# UBC-Thunderbots_PCB_Power__power-v3_1_pc.net
KiCad netlist of a schematic drawn in Altium Designer
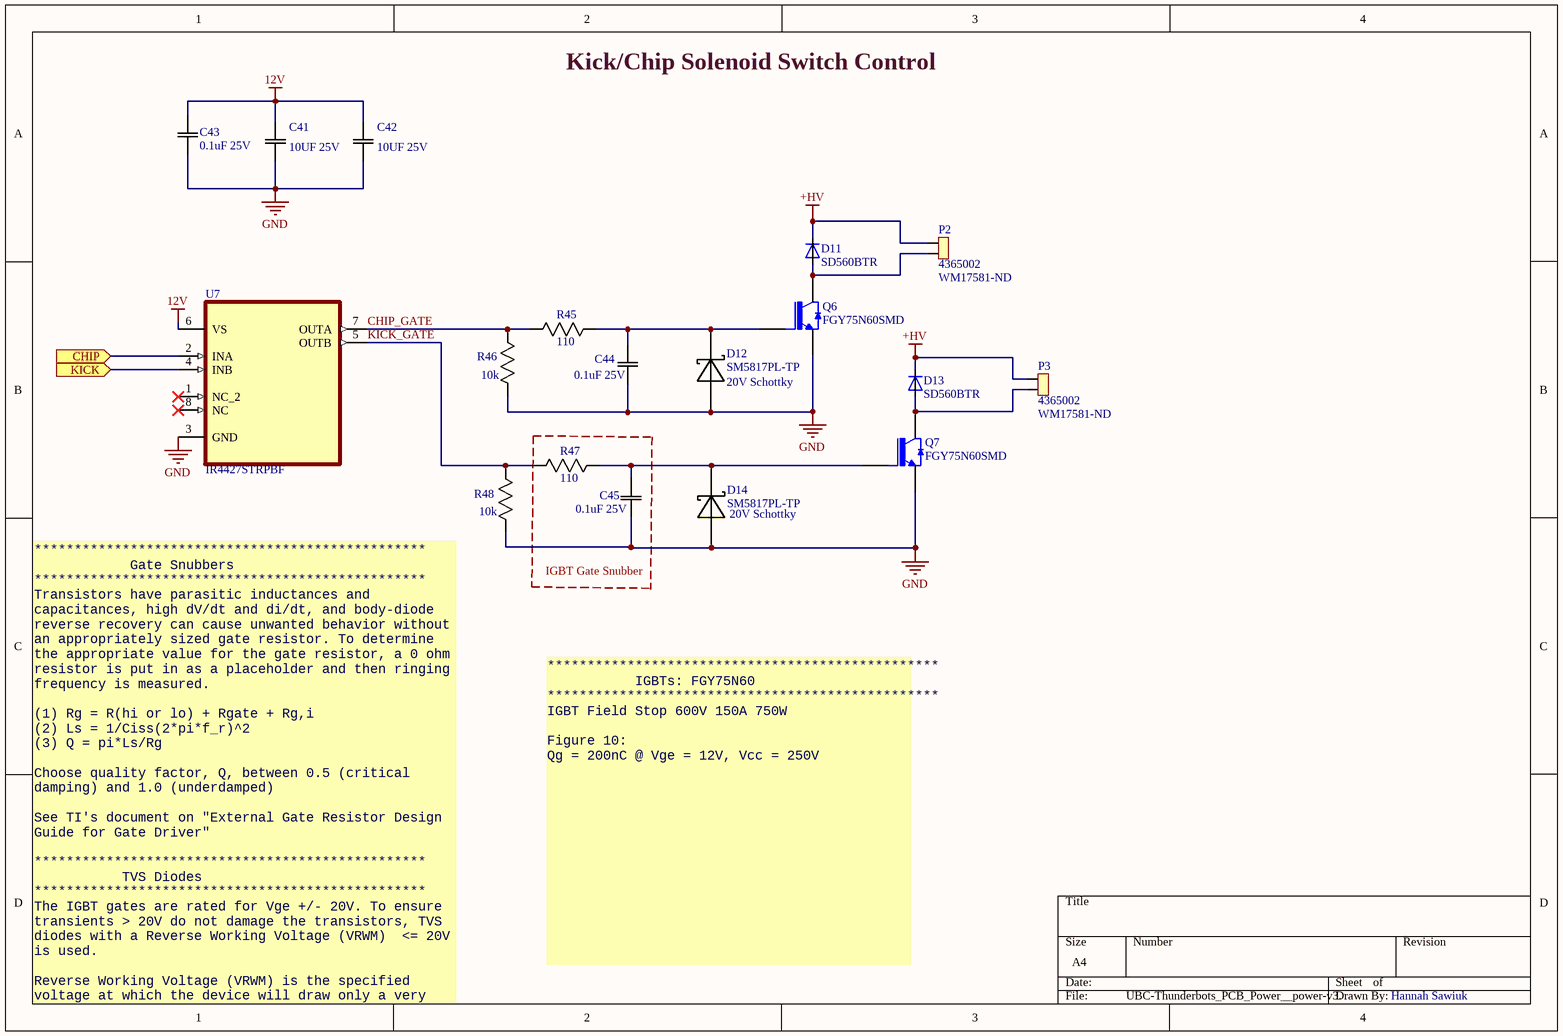
[diagram p0: UBC-Thunderbots_PCB_Power__power-v3.1_pcb__chicker.SchDoc]

(export (version "E")
  (design (tool "Eeschema 10.0.6"))
  (components
    (comp (ref "C41")
      (value "10UF 25V")
      (footprint "1206")
      (description "CAP CER 10UF 25V X5R 1206")
      (fields (field (name "TOLERANCE") "10%"))
      (libsource (lib "AltiumLibraries") (part "CAP 10uF 25V"))
    )
    (comp (ref "C42")
      (value "10UF 25V")
      (footprint "1206")
      (description "CAP CER 10UF 25V X5R 1206")
      (fields (field (name "TOLERANCE") "10%"))
      (libsource (lib "AltiumLibraries") (part "CAP 10uF 25V"))
    )
    (comp (ref "C43")
      (value "0.1uF 25V")
      (footprint "0805")
      (description "CAP CER 0.1UF 25V X7R 0805")
      (fields (field (name "TOLERANCE") "10%"))
      (libsource (lib "") (part "CAP 0.1uF 25V_1"))
    )
    (comp (ref "C44")
      (value "0.1uF 25V")
      (footprint "0805")
      (description "CAP CER 0.1UF 25V X7R 0805")
      (fields (field (name "TOLERANCE") "10%"))
      (libsource (lib "AltiumLibraries") (part "CAP 0.1uF 25V"))
    )
    (comp (ref "C45")
      (value "0.1uF 25V")
      (footprint "0805")
      (description "CAP CER 0.1UF 25V X7R 0805")
      (fields (field (name "TOLERANCE") "10%"))
      (libsource (lib "AltiumLibraries") (part "CAP 0.1uF 25V"))
    )
    (comp (ref "D11")
      (value "SD560BTR")
      (footprint "DO-214AA")
      (description "Diode Standard 600V 5A Surface Mount SMB")
      (libsource (lib "AltiumLibraries") (part "DIODE STANDARD 600V 5A"))
    )
    (comp (ref "D12")
      (value "SM5817PL-TP")
      (footprint "SOD-123")
      (description "Diode Schottky 20V 1A Surface Mount SOD-123FL")
      (fields (field (name "MF") "Micro Commercial Co"))
      (libsource (lib "AltiumLibraries") (part "DIODE SCHOTTKY 20V 1A"))
    )
    (comp (ref "D13")
      (value "SD560BTR")
      (footprint "DO-214AA")
      (description "Diode Standard 600V 5A Surface Mount SMB")
      (libsource (lib "AltiumLibraries") (part "DIODE STANDARD 600V 5A"))
    )
    (comp (ref "D14")
      (value "SM5817PL-TP")
      (footprint "SOD-123")
      (description "Diode Schottky 20V 1A Surface Mount SOD-123FL")
      (fields (field (name "MF") "Micro Commercial Co"))
      (libsource (lib "AltiumLibraries") (part "DIODE SCHOTTKY 20V 1A"))
    )
    (comp (ref "P2")
      (value "4365002")
      (footprint "43650-02")
      (description "MOLEX MICROFIT 2CKT RIGHT THRU")
      (fields
        (field (name "MF") "MOLEX")
        (field (name "MP") "4365002XX")
        (field (name "SUPPLIER PART NUMBER 2") "WM17581-ND")
      )
      (libsource (lib "AltiumLibraries") (part "CN MOLEX 4365002XX"))
    )
    (comp (ref "P3")
      (value "4365002")
      (footprint "43650-02")
      (description "MOLEX MICROFIT 2CKT RIGHT THRU")
      (fields
        (field (name "MF") "MOLEX")
        (field (name "MP") "4365002XX")
        (field (name "SUPPLIER PART NUMBER 2") "WM17581-ND")
      )
      (libsource (lib "AltiumLibraries") (part "CN MOLEX 4365002XX"))
    )
    (comp (ref "Q6")
      (value "FGY75N60SMD")
      (footprint "TO-247-3")
      (description "IGBT Field Stop 600V 150A 750W Through Hole PowerTO-247-3")
      (fields (field (name "MF") "ON Semiconductor") (field (name "POWER") "750W"))
      (libsource (lib "AltiumLibraries") (part "FGY75N60SMD"))
    )
    (comp (ref "Q7")
      (value "FGY75N60SMD")
      (footprint "TO-247-3")
      (description "IGBT Field Stop 600V 150A 750W Through Hole PowerTO-247-3")
      (fields (field (name "MF") "ON Semiconductor") (field (name "POWER") "750W"))
      (libsource (lib "AltiumLibraries") (part "FGY75N60SMD"))
    )
    (comp (ref "R45")
      (value "110")
      (footprint "0805")
      (description "RES SMD 110 OHM 1% 1/8W 0805")
      (fields (field (name "TOLERANCE") "1%"))
      (libsource (lib "AltiumLibraries") (part "RES 110.0 1/8W - 1%"))
    )
    (comp (ref "R46")
      (value "10k")
      (footprint "0805")
      (description "RES SMD 10K OHM 1% 1/8W 0805")
      (fields (field (name "TOLERANCE") "1%"))
      (libsource (lib "AltiumLibraries") (part "RES 10k 1/8W - 1%"))
    )
    (comp (ref "R47")
      (value "110")
      (footprint "0805")
      (description "RES SMD 110 OHM 1% 1/8W 0805")
      (fields (field (name "TOLERANCE") "1%"))
      (libsource (lib "") (part "RES 110.0 1/8W - 1%_1"))
    )
    (comp (ref "R48")
      (value "10k")
      (footprint "0805")
      (description "RES SMD 10K OHM 1% 1/8W 0805")
      (fields (field (name "TOLERANCE") "1%"))
      (libsource (lib "AltiumLibraries") (part "RES 10k 1/8W - 1%"))
    )
    (comp (ref "U7")
      (value "IR4427STRPBF")
      (footprint "8-SOIC")
      (description "Low-Side Gate Driver IC Non-Inverting 8-SOIC")
      (fields (field (name "MF") "Infineon Technologies"))
      (libsource (lib "AltiumLibraries") (part "IR4427STRPBF"))
    )
  )
  (nets
    (net (code "1") (name "+HV") (class "Default")
      (node (ref "D11") (pin "C") (pinfunction "C_C") (pintype "passive"))
      (node (ref "D13") (pin "C") (pinfunction "C_C") (pintype "passive"))
      (node (ref "P2") (pin "1") (pinfunction "1_1") (pintype "passive"))
      (node (ref "P3") (pin "1") (pinfunction "1_1") (pintype "passive"))
    )
    (net (code "2") (name "/CHIP") (class "Default")
      (node (ref "U7") (pin "2") (pinfunction "INA_2") (pintype "input"))
    )
    (net (code "3") (name "/CHIP_GATE") (class "Default")
      (node (ref "R45") (pin "2") (pinfunction "R2_2") (pintype "passive"))
      (node (ref "R46") (pin "1") (pinfunction "R1_1") (pintype "passive"))
      (node (ref "U7") (pin "7") (pinfunction "OUTA_7") (pintype "output"))
    )
    (net (code "4") (name "/KICK") (class "Default")
      (node (ref "U7") (pin "4") (pinfunction "INB_4") (pintype "input"))
    )
    (net (code "5") (name "/KICK_GATE") (class "Default")
      (node (ref "R47") (pin "2") (pinfunction "R2_2") (pintype "passive"))
      (node (ref "R48") (pin "1") (pinfunction "R1_1") (pintype "passive"))
      (node (ref "U7") (pin "5") (pinfunction "OUTB_5") (pintype "output"))
    )
    (net (code "6") (name "12V") (class "Default")
      (node (ref "C41") (pin "1") (pinfunction "C1_1") (pintype "passive"))
      (node (ref "C42") (pin "1") (pinfunction "C1_1") (pintype "passive"))
      (node (ref "C43") (pin "2") (pinfunction "C2_2") (pintype "passive"))
      (node (ref "U7") (pin "6") (pinfunction "VS_6") (pintype "power_in"))
    )
    (net (code "7") (name "GND") (class "Default")
      (node (ref "C41") (pin "2") (pinfunction "C2_2") (pintype "passive"))
      (node (ref "C42") (pin "2") (pinfunction "C2_2") (pintype "passive"))
      (node (ref "C43") (pin "1") (pinfunction "C1_1") (pintype "passive"))
      (node (ref "C44") (pin "1") (pinfunction "C1_1") (pintype "passive"))
      (node (ref "C45") (pin "1") (pinfunction "C1_1") (pintype "passive"))
      (node (ref "D12") (pin "A") (pinfunction "A_A") (pintype "passive"))
      (node (ref "D14") (pin "A") (pinfunction "A_A") (pintype "passive"))
      (node (ref "Q6") (pin "3") (pinfunction "E_3") (pintype "passive"))
      (node (ref "Q7") (pin "3") (pinfunction "E_3") (pintype "passive"))
      (node (ref "R46") (pin "2") (pinfunction "R2_2") (pintype "passive"))
      (node (ref "R48") (pin "2") (pinfunction "R2_2") (pintype "passive"))
      (node (ref "U7") (pin "3") (pinfunction "GND_3") (pintype "passive"))
    )
    (net (code "8") (name "Net-(C44-C2)") (class "Default")
      (node (ref "C44") (pin "2") (pinfunction "C2_2") (pintype "passive"))
      (node (ref "D12") (pin "C") (pinfunction "K_C") (pintype "passive"))
      (node (ref "Q6") (pin "1") (pinfunction "G_1") (pintype "passive"))
      (node (ref "R45") (pin "1") (pinfunction "R1_1") (pintype "passive"))
    )
    (net (code "9") (name "Net-(C45-C2)") (class "Default")
      (node (ref "C45") (pin "2") (pinfunction "C2_2") (pintype "passive"))
      (node (ref "D14") (pin "C") (pinfunction "K_C") (pintype "passive"))
      (node (ref "Q7") (pin "1") (pinfunction "G_1") (pintype "passive"))
      (node (ref "R47") (pin "1") (pinfunction "R1_1") (pintype "passive"))
    )
    (net (code "10") (name "Net-(Q6-C)") (class "Default")
      (node (ref "D11") (pin "A") (pinfunction "A_A") (pintype "passive"))
      (node (ref "P2") (pin "2") (pinfunction "2_2") (pintype "passive"))
      (node (ref "Q6") (pin "2") (pinfunction "C_2") (pintype "passive"))
    )
    (net (code "11") (name "Net-(Q7-C)") (class "Default")
      (node (ref "D13") (pin "A") (pinfunction "A_A") (pintype "passive"))
      (node (ref "P3") (pin "2") (pinfunction "2_2") (pintype "passive"))
      (node (ref "Q7") (pin "2") (pinfunction "C_2") (pintype "passive"))
    )
    (net (code "12") (name "unconnected-(U7-NC-Pad8)") (class "Default")
      (node (ref "U7") (pin "8") (pinfunction "NC_8") (pintype "input+no_connect"))
    )
    (net (code "13") (name "unconnected-(U7-NC_2-Pad1)") (class "Default")
      (node (ref "U7") (pin "1") (pinfunction "NC_2_1") (pintype "input+no_connect"))
    )
  )
)
